# v1_5_Flash_Buzzer.net
KiCad netlist of a schematic drawn in Altium Designer
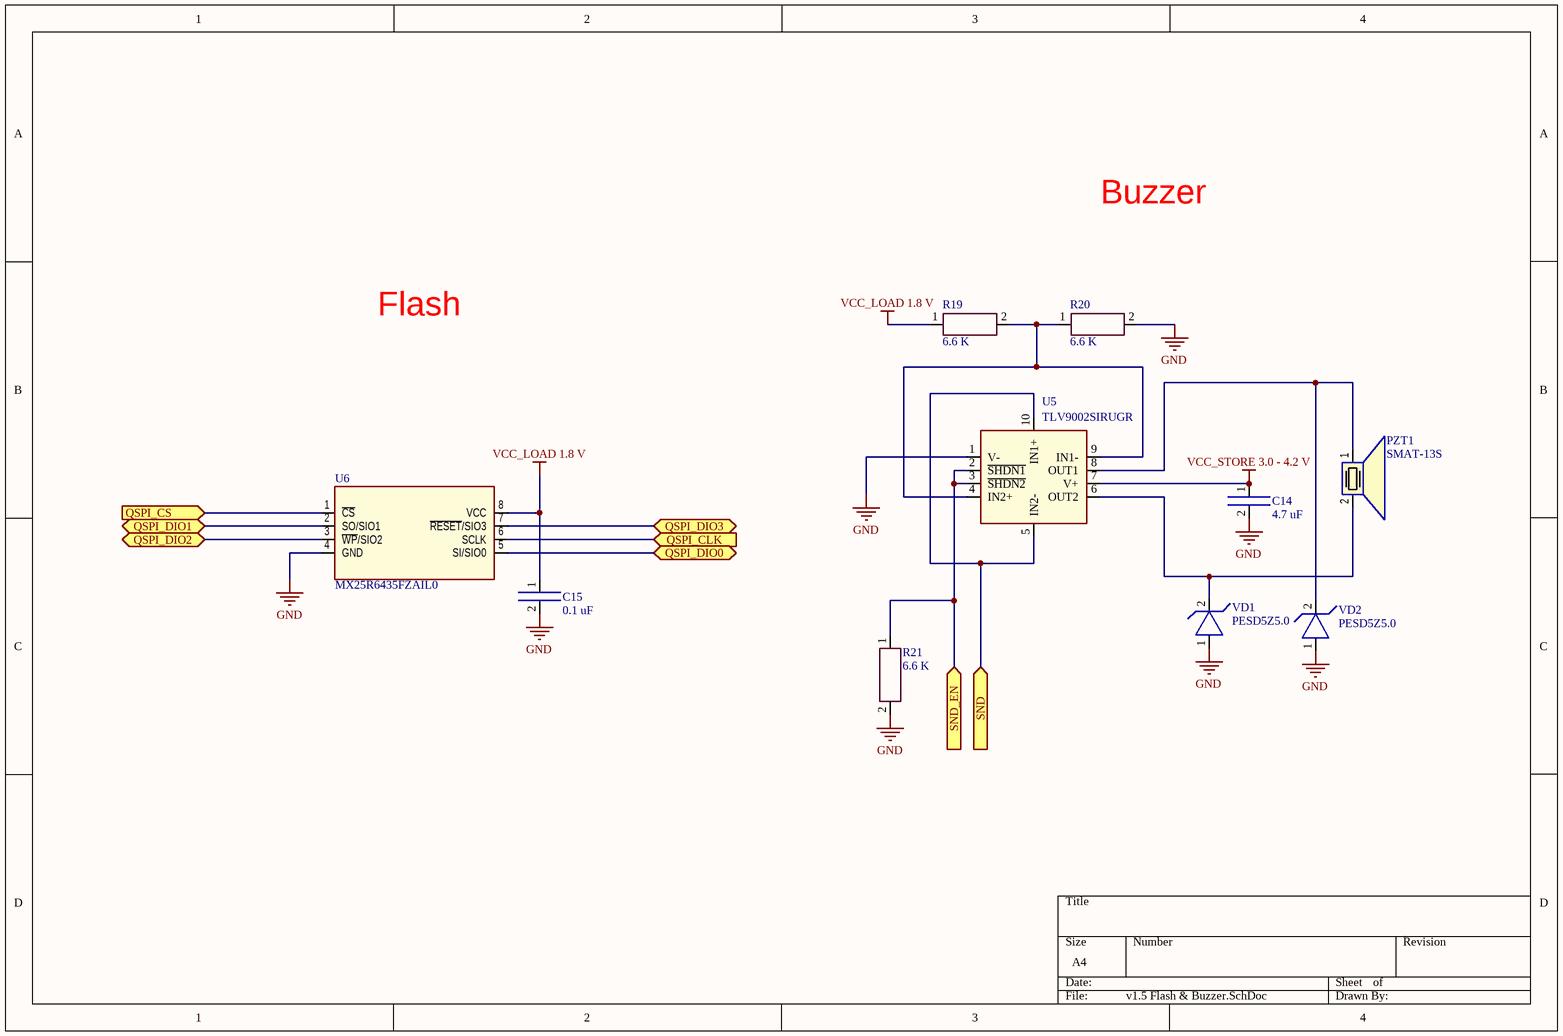
[diagram p0: v1.5 Flash & Buzzer.SchDoc]

(export (version "E")
  (design (tool "Eeschema 10.0.6"))
  (components
    (comp (ref "C14")
      (value "4.7 uF")
      (footprint "Ungravity Library:0402")
      (libsource (lib "Ungravity Library") (part "Capasistor"))
    )
    (comp (ref "C15")
      (value "0.1 uF")
      (footprint "Ungravity Library:0402")
      (libsource (lib "Ungravity Library") (part "Capasistor"))
    )
    (comp (ref "PZT1")
      (value "SMAT-13S")
      (footprint "Ungravity Library:SMAT-13-mount by wire")
      (libsource (lib "Ungravity Library") (part "Piezo transducer"))
    )
    (comp (ref "R19")
      (value "6.6 K")
      (footprint "Ungravity Library:0402")
      (libsource (lib "Ungravity Library") (part "Resistor"))
    )
    (comp (ref "R20")
      (value "6.6 K")
      (footprint "Ungravity Library:0402")
      (libsource (lib "Ungravity Library") (part "Resistor"))
    )
    (comp (ref "R21")
      (value "6.6 K")
      (footprint "Ungravity Library:0402")
      (libsource (lib "Ungravity Library") (part "Resistor"))
    )
    (comp (ref "U5")
      (value "TLV9002SIRUGR")
      (footprint "Ungravity Library:X2QFN")
      (libsource (lib "Ungravity Library") (part "TLV9002S"))
    )
    (comp (ref "U6")
      (value "MX25R6435FZAIL0")
      (footprint "Ungravity Library:MX25R6435F-ZA")
      (libsource (lib "Ungravity Library") (part "MX25R6435F-ZA"))
    )
    (comp (ref "VD1")
      (value "PESD5Z5.0")
      (footprint "Ungravity Library:SOD-523")
      (libsource (lib "Ungravity Library") (part "Stabilitron"))
    )
    (comp (ref "VD2")
      (value "PESD5Z5.0")
      (footprint "Ungravity Library:SOD-523")
      (libsource (lib "Ungravity Library") (part "Stabilitron"))
    )
  )
  (nets
    (net (code "1") (name "/QSPI_CLK") (class "Default")
      (node (ref "U6") (pin "6") (pinfunction "SCLK_6") (pintype "passive"))
    )
    (net (code "2") (name "/QSPI_CS") (class "Default")
      (node (ref "U6") (pin "1") (pinfunction "~{CS}_1") (pintype "passive"))
    )
    (net (code "3") (name "/QSPI_DIO0") (class "Default")
      (node (ref "U6") (pin "5") (pinfunction "SI/SIO0_5") (pintype "passive"))
    )
    (net (code "4") (name "/QSPI_DIO1") (class "Default")
      (node (ref "U6") (pin "2") (pinfunction "SO/SIO1_2") (pintype "passive"))
    )
    (net (code "5") (name "/QSPI_DIO2") (class "Default")
      (node (ref "U6") (pin "3") (pinfunction "~{WP}/SIO2_3") (pintype "passive"))
    )
    (net (code "6") (name "/QSPI_DIO3") (class "Default")
      (node (ref "U6") (pin "7") (pinfunction "~{RESET}/SIO3_7") (pintype "passive"))
    )
    (net (code "7") (name "/SND") (class "Default")
      (node (ref "U5") (pin "10") (pinfunction "IN1+_10") (pintype "passive"))
      (node (ref "U5") (pin "5") (pinfunction "IN2-_5") (pintype "passive"))
    )
    (net (code "8") (name "/SND_EN") (class "Default")
      (node (ref "R21") (pin "1") (pinfunction "1_1") (pintype "passive"))
      (node (ref "U5") (pin "2") (pinfunction "~{SHDN1}_2") (pintype "passive"))
      (node (ref "U5") (pin "3") (pinfunction "~{SHDN2}_3") (pintype "passive"))
    )
    (net (code "9") (name "GND") (class "Default")
      (node (ref "C14") (pin "2") (pinfunction "2_2") (pintype "passive"))
      (node (ref "C15") (pin "2") (pinfunction "2_2") (pintype "passive"))
      (node (ref "R20") (pin "2") (pinfunction "2_2") (pintype "passive"))
      (node (ref "R21") (pin "2") (pinfunction "2_2") (pintype "passive"))
      (node (ref "U5") (pin "1") (pinfunction "V-_1") (pintype "passive"))
      (node (ref "U6") (pin "4") (pinfunction "GND_4") (pintype "passive"))
      (node (ref "VD1") (pin "1") (pinfunction "1_1") (pintype "passive"))
      (node (ref "VD2") (pin "1") (pinfunction "1_1") (pintype "passive"))
    )
    (net (code "10") (name "Net-(U5-IN1-)") (class "Default")
      (node (ref "R19") (pin "2") (pinfunction "2_2") (pintype "passive"))
      (node (ref "R20") (pin "1") (pinfunction "1_1") (pintype "passive"))
      (node (ref "U5") (pin "4") (pinfunction "IN2+_4") (pintype "passive"))
      (node (ref "U5") (pin "9") (pinfunction "IN1-_9") (pintype "passive"))
    )
    (net (code "11") (name "Net-(U5-OUT1)") (class "Default")
      (node (ref "PZT1") (pin "1") (pinfunction "1_1") (pintype "passive"))
      (node (ref "U5") (pin "8") (pinfunction "OUT1_8") (pintype "passive"))
      (node (ref "VD2") (pin "2") (pinfunction "2_2") (pintype "passive"))
    )
    (net (code "12") (name "Net-(U5-OUT2)") (class "Default")
      (node (ref "PZT1") (pin "2") (pinfunction "2_2") (pintype "passive"))
      (node (ref "U5") (pin "6") (pinfunction "OUT2_6") (pintype "passive"))
      (node (ref "VD1") (pin "2") (pinfunction "2_2") (pintype "passive"))
    )
    (net (code "13") (name "VCC_LOAD 1.8 V") (class "Default")
      (node (ref "C15") (pin "1") (pinfunction "1_1") (pintype "passive"))
      (node (ref "R19") (pin "1") (pinfunction "1_1") (pintype "passive"))
      (node (ref "U6") (pin "8") (pinfunction "VCC_8") (pintype "passive"))
    )
    (net (code "14") (name "VCC_STORE 3.0 - 4.2 V") (class "Default")
      (node (ref "C14") (pin "1") (pinfunction "1_1") (pintype "passive"))
      (node (ref "U5") (pin "7") (pinfunction "V+_7") (pintype "passive"))
    )
  )
)
